# thermal-flashlight.net
KiCad netlist of a schematic drawn in EAGLE
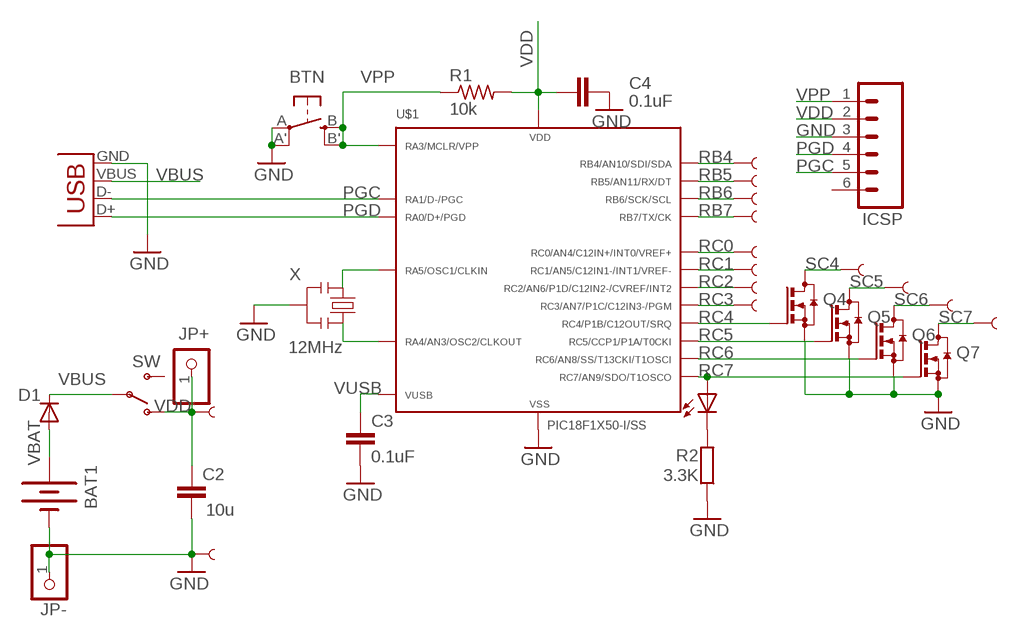
[diagram p0: schematic, sheet 1]

(export (version "E")
  (design (tool "Eeschema 10.0.6"))
  (components
    (comp (ref "BAT1")
      (value "BATTERY20MM_4LEGS")
      (footprint "eagle-import:BATTCON_20MM_4LEGS")
      (libsource (lib "eagle-import") (part "BATTERY20MM_4LEGS"))
    )
    (comp (ref "BTN")
      (value "EVQQ2")
      (footprint "eagle-import:EVQ-Q2")
      (libsource (lib "eagle-import") (part "EVQQ2"))
    )
    (comp (ref "C2")
      (value "10u")
      (footprint "eagle-import:C0805")
      (libsource (lib "eagle-import") (part "resistor_C-EUC0805"))
    )
    (comp (ref "C3")
      (value "0.1uF")
      (footprint "eagle-import:C0805")
      (libsource (lib "eagle-import") (part "C-EUC0805"))
    )
    (comp (ref "C4")
      (value "0.1uF")
      (footprint "eagle-import:C0805")
      (libsource (lib "eagle-import") (part "C-EUC0805"))
    )
    (comp (ref "D1")
      (value "DIODESOT23")
      (footprint "eagle-import:SOT23-3")
      (libsource (lib "eagle-import") (part "DIODESOT23"))
    )
    (comp (ref "ICSP")
      (value "M06SIP")
      (footprint "eagle-import:1X06")
      (libsource (lib "eagle-import") (part "M06SIP"))
    )
    (comp (ref "JP+")
      (value "PINHD-1X1CB")
      (footprint "eagle-import:1X01-CLEANBIG")
      (libsource (lib "eagle-import") (part "PINHD-1X1CB"))
    )
    (comp (ref "JP-")
      (value "PINHD-1X1CB")
      (footprint "eagle-import:1X01-CLEANBIG")
      (libsource (lib "eagle-import") (part "PINHD-1X1CB"))
    )
    (comp (ref "LED")
      (value "0805")
      (footprint "eagle-import:CHIPLED_0805")
      (libsource (lib "eagle-import") (part "LEDCHIPLED_0805"))
    )
    (comp (ref "PB4")
      (value "SEWTAP61")
      (footprint "eagle-import:PETAL-SMALL-2SIDE1")
      (libsource (lib "eagle-import") (part "SEWTAP61"))
    )
    (comp (ref "PB5")
      (value "SEWTAP6")
      (footprint "eagle-import:PETAL-SMALL-2SIDE1")
      (libsource (lib "eagle-import") (part "SEWTAP61"))
    )
    (comp (ref "PB6")
      (value "SEWTAP6")
      (footprint "eagle-import:PETAL-SMALL-2SIDE1")
      (libsource (lib "eagle-import") (part "SEWTAP61"))
    )
    (comp (ref "PB7")
      (value "SEWTAP6")
      (footprint "eagle-import:PETAL-SMALL-2SIDE1")
      (libsource (lib "eagle-import") (part "SEWTAP61"))
    )
    (comp (ref "PC0")
      (value "SEWTAP6")
      (footprint "eagle-import:PETAL-SMALL-2SIDE1")
      (libsource (lib "eagle-import") (part "SEWTAP61"))
    )
    (comp (ref "PC1")
      (value "SEWTAP6")
      (footprint "eagle-import:PETAL-SMALL-2SIDE1")
      (libsource (lib "eagle-import") (part "SEWTAP61"))
    )
    (comp (ref "PC2")
      (value "SEWTAP6")
      (footprint "eagle-import:PETAL-SMALL-2SIDE1")
      (libsource (lib "eagle-import") (part "SEWTAP61"))
    )
    (comp (ref "PC3")
      (value "SEWTAP6")
      (footprint "eagle-import:PETAL-SMALL-2SIDE1")
      (libsource (lib "eagle-import") (part "SEWTAP61"))
    )
    (comp (ref "PG")
      (value "SEWTAP6")
      (footprint "eagle-import:PETAL-SMALL-2SIDE11")
      (libsource (lib "eagle-import") (part "SEWTAP611"))
    )
    (comp (ref "PSC4")
      (value "SEWTAP6")
      (footprint "eagle-import:PETAL-SMALL-2SIDE1")
      (libsource (lib "eagle-import") (part "SEWTAP61"))
    )
    (comp (ref "PSC5")
      (value "SEWTAP6")
      (footprint "eagle-import:PETAL-SMALL-2SIDE1")
      (libsource (lib "eagle-import") (part "SEWTAP61"))
    )
    (comp (ref "PSC6")
      (value "SEWTAP6")
      (footprint "eagle-import:PETAL-SMALL-2SIDE1")
      (libsource (lib "eagle-import") (part "SEWTAP61"))
    )
    (comp (ref "PSC7")
      (value "SEWTAP6")
      (footprint "eagle-import:PETAL-SMALL-2SIDE1")
      (libsource (lib "eagle-import") (part "SEWTAP61"))
    )
    (comp (ref "PVCC")
      (value "SEWTAP6")
      (footprint "eagle-import:PETAL-SMALL-2SIDE11")
      (libsource (lib "eagle-import") (part "SEWTAP611"))
    )
    (comp (ref "Q4")
      (value "BSS123")
      (footprint "eagle-import:SOT23")
      (libsource (lib "eagle-import") (part "BSS123"))
    )
    (comp (ref "Q5")
      (value "BSS123")
      (footprint "eagle-import:SOT23")
      (libsource (lib "eagle-import") (part "BSS123"))
    )
    (comp (ref "Q6")
      (value "BSS123")
      (footprint "eagle-import:SOT23")
      (libsource (lib "eagle-import") (part "BSS123"))
    )
    (comp (ref "Q7")
      (value "BSS123")
      (footprint "eagle-import:SOT23")
      (libsource (lib "eagle-import") (part "BSS123"))
    )
    (comp (ref "R1")
      (value "10k")
      (footprint "eagle-import:R0805@1")
      (libsource (lib "eagle-import") (part "R-US_R0805"))
    )
    (comp (ref "R2")
      (value "3.3K")
      (footprint "eagle-import:R0805")
      (libsource (lib "eagle-import") (part "R-EU_R0805"))
    )
    (comp (ref "SW")
      (value "SPDT")
      (footprint "eagle-import:SWITCH-SPDT-SMD")
      (libsource (lib "eagle-import") (part "SWITCH-SPSTSMD2"))
    )
    (comp (ref "U$1")
      (value "PIC18F1X50-I/SS")
      (footprint "eagle-import:SSOP20")
      (libsource (lib "eagle-import") (part "PIC18F1X50-I/SS"))
    )
    (comp (ref "X")
      (value "12MHz")
      (footprint "eagle-import:RESONATOR-SMD")
      (libsource (lib "eagle-import") (part "RESONATORSMD"))
    )
    (comp (ref "X1")
      (value "USBSMD")
      (footprint "eagle-import:USB-MINIB")
      (libsource (lib "eagle-import") (part "USBSMD"))
    )
  )
  (nets
    (net (code "1") (name "/PGC") (class "Default")
      (node (ref "ICSP") (pin "5") (pinfunction "5_5") (pintype "passive"))
      (node (ref "U$1") (pin "18") (pinfunction "P$18_18") (pintype "bidirectional"))
      (node (ref "X1") (pin "D-") (pinfunction "D-_D-") (pintype "bidirectional"))
    )
    (net (code "2") (name "/PGD") (class "Default")
      (node (ref "ICSP") (pin "4") (pinfunction "4_4") (pintype "passive"))
      (node (ref "U$1") (pin "19") (pinfunction "P$19_19") (pintype "bidirectional"))
      (node (ref "X1") (pin "D+") (pinfunction "D+_D+") (pintype "bidirectional"))
    )
    (net (code "3") (name "/RB4") (class "Default")
      (node (ref "PB4") (pin "1") (pinfunction "1_1") (pintype "bidirectional"))
      (node (ref "U$1") (pin "13") (pinfunction "P$13_13") (pintype "bidirectional"))
    )
    (net (code "4") (name "/RB5") (class "Default")
      (node (ref "PB5") (pin "1") (pinfunction "1_1") (pintype "bidirectional"))
      (node (ref "U$1") (pin "12") (pinfunction "P$12_12") (pintype "bidirectional"))
    )
    (net (code "5") (name "/RB6") (class "Default")
      (node (ref "PB6") (pin "1") (pinfunction "1_1") (pintype "bidirectional"))
      (node (ref "U$1") (pin "11") (pinfunction "P$11_11") (pintype "bidirectional"))
    )
    (net (code "6") (name "/RB7") (class "Default")
      (node (ref "PB7") (pin "1") (pinfunction "1_1") (pintype "bidirectional"))
      (node (ref "U$1") (pin "10") (pinfunction "P$10_10") (pintype "bidirectional"))
    )
    (net (code "7") (name "/RC0") (class "Default")
      (node (ref "PC0") (pin "1") (pinfunction "1_1") (pintype "bidirectional"))
      (node (ref "U$1") (pin "16") (pinfunction "P$16_16") (pintype "bidirectional"))
    )
    (net (code "8") (name "/RC1") (class "Default")
      (node (ref "PC1") (pin "1") (pinfunction "1_1") (pintype "bidirectional"))
      (node (ref "U$1") (pin "15") (pinfunction "P$15_15") (pintype "bidirectional"))
    )
    (net (code "9") (name "/RC2") (class "Default")
      (node (ref "PC2") (pin "1") (pinfunction "1_1") (pintype "bidirectional"))
      (node (ref "U$1") (pin "14") (pinfunction "P$14_14") (pintype "bidirectional"))
    )
    (net (code "10") (name "/RC3") (class "Default")
      (node (ref "PC3") (pin "1") (pinfunction "1_1") (pintype "bidirectional"))
      (node (ref "U$1") (pin "7") (pinfunction "P$7_7") (pintype "bidirectional"))
    )
    (net (code "11") (name "/RC4") (class "Default")
      (node (ref "Q4") (pin "1") (pinfunction "G_1") (pintype "passive"))
      (node (ref "U$1") (pin "6") (pinfunction "P$6_6") (pintype "bidirectional"))
    )
    (net (code "12") (name "/RC5") (class "Default")
      (node (ref "Q5") (pin "1") (pinfunction "G_1") (pintype "passive"))
      (node (ref "U$1") (pin "5") (pinfunction "P$5_5") (pintype "bidirectional"))
    )
    (net (code "13") (name "/RC6") (class "Default")
      (node (ref "Q6") (pin "1") (pinfunction "G_1") (pintype "passive"))
      (node (ref "U$1") (pin "8") (pinfunction "P$8_8") (pintype "bidirectional"))
    )
    (net (code "14") (name "/RC7") (class "Default")
      (node (ref "LED") (pin "A") (pinfunction "A_A") (pintype "passive"))
      (node (ref "Q7") (pin "1") (pinfunction "G_1") (pintype "passive"))
      (node (ref "U$1") (pin "9") (pinfunction "P$9_9") (pintype "bidirectional"))
    )
    (net (code "15") (name "/SC4") (class "Default")
      (node (ref "PSC4") (pin "1") (pinfunction "1_1") (pintype "bidirectional"))
      (node (ref "Q4") (pin "3") (pinfunction "D_3") (pintype "passive"))
    )
    (net (code "16") (name "/SC5") (class "Default")
      (node (ref "PSC5") (pin "1") (pinfunction "1_1") (pintype "bidirectional"))
      (node (ref "Q5") (pin "3") (pinfunction "D_3") (pintype "passive"))
    )
    (net (code "17") (name "/SC6") (class "Default")
      (node (ref "PSC6") (pin "1") (pinfunction "1_1") (pintype "bidirectional"))
      (node (ref "Q6") (pin "3") (pinfunction "D_3") (pintype "passive"))
    )
    (net (code "18") (name "/SC7") (class "Default")
      (node (ref "PSC7") (pin "1") (pinfunction "1_1") (pintype "bidirectional"))
      (node (ref "Q7") (pin "3") (pinfunction "D_3") (pintype "passive"))
    )
    (net (code "19") (name "/VBAT") (class "Default")
      (node (ref "BAT1") (pin "1") (pinfunction "+_1") (pintype "power_in"))
      (node (ref "D1") (pin "1") (pinfunction "A_1") (pintype "passive"))
    )
    (net (code "20") (name "/VBUS") (class "Default")
      (node (ref "D1") (pin "3") (pinfunction "C_3") (pintype "passive"))
      (node (ref "SW") (pin "2") (pinfunction "P_2") (pintype "passive"))
      (node (ref "X1") (pin "VBUS") (pinfunction "VBUS_VBUS") (pintype "bidirectional"))
    )
    (net (code "21") (name "/VDD") (class "Default")
      (node (ref "C2") (pin "1") (pinfunction "1_1") (pintype "passive"))
      (node (ref "C4") (pin "1") (pinfunction "1_1") (pintype "passive"))
      (node (ref "ICSP") (pin "2") (pinfunction "2_2") (pintype "passive"))
      (node (ref "JP+") (pin "1") (pinfunction "1_1") (pintype "passive"))
      (node (ref "PVCC") (pin "1") (pinfunction "1_1") (pintype "bidirectional"))
      (node (ref "R1") (pin "2") (pinfunction "2_2") (pintype "passive"))
      (node (ref "SW") (pin "1") (pinfunction "O_1") (pintype "passive"))
      (node (ref "U$1") (pin "1") (pinfunction "P$1_1") (pintype "power_in"))
    )
    (net (code "22") (name "/VPP") (class "Default")
      (node (ref "BTN") (pin "B") (pinfunction "S_B") (pintype "passive"))
      (node (ref "BTN") (pin "B'") (pinfunction "S1_B'") (pintype "passive"))
      (node (ref "ICSP") (pin "1") (pinfunction "1_1") (pintype "passive"))
      (node (ref "R1") (pin "1") (pinfunction "1_1") (pintype "passive"))
      (node (ref "U$1") (pin "4") (pinfunction "P$4_4") (pintype "bidirectional"))
    )
    (net (code "23") (name "/VUSB") (class "Default")
      (node (ref "C3") (pin "1") (pinfunction "1_1") (pintype "passive"))
      (node (ref "U$1") (pin "17") (pinfunction "P$17_17") (pintype "bidirectional"))
    )
    (net (code "24") (name "GND") (class "Default")
      (node (ref "BAT1") (pin "2") (pinfunction "-_2") (pintype "power_in"))
      (node (ref "BTN") (pin "A") (pinfunction "P_A") (pintype "passive"))
      (node (ref "BTN") (pin "A'") (pinfunction "P1_A'") (pintype "passive"))
      (node (ref "C2") (pin "2") (pinfunction "2_2") (pintype "passive"))
      (node (ref "C3") (pin "2") (pinfunction "2_2") (pintype "passive"))
      (node (ref "C4") (pin "2") (pinfunction "2_2") (pintype "passive"))
      (node (ref "ICSP") (pin "3") (pinfunction "3_3") (pintype "passive"))
      (node (ref "JP-") (pin "1") (pinfunction "1_1") (pintype "passive"))
      (node (ref "PG") (pin "1") (pinfunction "1_1") (pintype "bidirectional"))
      (node (ref "Q4") (pin "2") (pinfunction "S_2") (pintype "passive"))
      (node (ref "Q5") (pin "2") (pinfunction "S_2") (pintype "passive"))
      (node (ref "Q6") (pin "2") (pinfunction "S_2") (pintype "passive"))
      (node (ref "Q7") (pin "2") (pinfunction "S_2") (pintype "passive"))
      (node (ref "R2") (pin "1") (pinfunction "1_1") (pintype "passive"))
      (node (ref "U$1") (pin "20") (pinfunction "P$20_20") (pintype "power_in"))
      (node (ref "X") (pin "2") (pinfunction "2_2") (pintype "passive"))
      (node (ref "X1") (pin "GND") (pinfunction "GND_GND") (pintype "bidirectional"))
    )
    (net (code "25") (name "Net-(LED-PadC)") (class "Default")
      (node (ref "LED") (pin "C") (pinfunction "C_C") (pintype "passive"))
      (node (ref "R2") (pin "2") (pinfunction "2_2") (pintype "passive"))
    )
    (net (code "26") (name "Net-(U$1-P$2)") (class "Default")
      (node (ref "U$1") (pin "2") (pinfunction "P$2_2") (pintype "bidirectional"))
      (node (ref "X") (pin "1") (pinfunction "1_1") (pintype "passive"))
    )
    (net (code "27") (name "Net-(U$1-P$3)") (class "Default")
      (node (ref "U$1") (pin "3") (pinfunction "P$3_3") (pintype "bidirectional"))
      (node (ref "X") (pin "3") (pinfunction "3_3") (pintype "passive"))
    )
    (net (code "28") (name "unconnected-(ICSP-Pad6)") (class "Default")
      (node (ref "ICSP") (pin "6") (pinfunction "6_6") (pintype "passive"))
    )
    (net (code "29") (name "unconnected-(SW-S-Pad3)") (class "Default")
      (node (ref "SW") (pin "3") (pinfunction "S_3") (pintype "passive"))
    )
  )
)
